# GPIB.net
KiCad netlist of a schematic drawn in Altium Designer
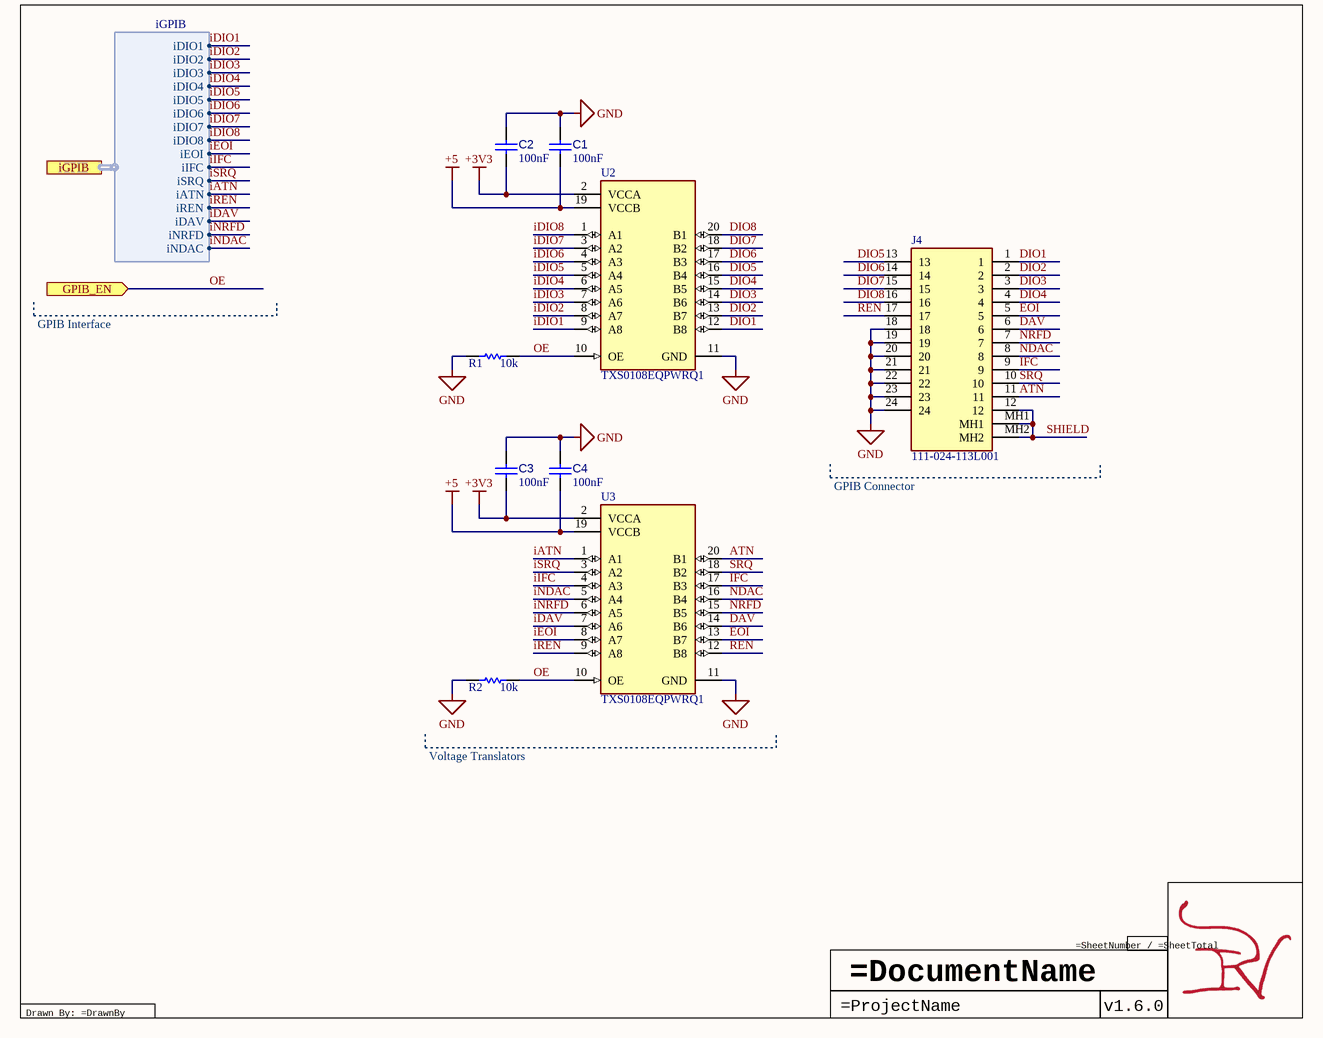
[diagram p0: GPIB.SchDoc]

(export (version "E")
  (design (tool "Eeschema 10.0.6"))
  (components
    (comp (ref "C1")
      (value "100nF")
      (footprint "CAP 0402_1005")
      (fields (field (name "TOLERANCE") "10%") (field (name "Comment") "CAP-NP-2"))
      (libsource (lib "IIT Motorsports") (part "CAP-NP-2"))
    )
    (comp (ref "C2")
      (value "100nF")
      (footprint "CAP 0402_1005")
      (fields (field (name "TOLERANCE") "10%") (field (name "Comment") "CAP-NP-2"))
      (libsource (lib "IIT Motorsports") (part "CAP-NP-2"))
    )
    (comp (ref "C3")
      (value "100nF")
      (footprint "CAP 0402_1005")
      (fields (field (name "TOLERANCE") "10%") (field (name "Comment") "CAP-NP-2"))
      (libsource (lib "IIT Motorsports") (part "CAP-NP-2"))
    )
    (comp (ref "C4")
      (value "100nF")
      (footprint "CAP 0402_1005")
      (fields (field (name "TOLERANCE") "10%") (field (name "Comment") "CAP-NP-2"))
      (libsource (lib "IIT Motorsports") (part "CAP-NP-2"))
    )
    (comp (ref "J4")
      (value "111-024-113L001")
      (footprint "111024113L001")
      (description "Telecom and Datacom Connector")
      (fields (field (name "MOUSER PART NUMBER") "636-111-024-113L001"))
      (libsource (lib "IIT Motorsports") (part "111-024-113L001"))
    )
    (comp (ref "R1")
      (value "10k")
      (footprint "RES 0402_1005")
      (fields
        (field (name "TOLERANCE") "1%")
        (field (name "POWER") "100mW")
        (field (name "Comment") "10K-0402-0.1/1")
      )
      (libsource (lib "IIT Motorsports") (part "RES"))
    )
    (comp (ref "R2")
      (value "10k")
      (footprint "RES 0402_1005")
      (fields
        (field (name "TOLERANCE") "1%")
        (field (name "POWER") "100mW")
        (field (name "Comment") "10K-0402-0.1/1")
      )
      (libsource (lib "IIT Motorsports") (part "RES"))
    )
    (comp (ref "U2")
      (value "TXS0108EQPWRQ1")
      (footprint "FP-PW0020A-IPC_B")
      (description "Interface Circuit, PDSO20")
      (libsource (lib "IIT Motorsports") (part "b852cf3f2c97e4a3d4172ee3f19d589"))
    )
    (comp (ref "U3")
      (value "TXS0108EQPWRQ1")
      (footprint "FP-PW0020A-IPC_B")
      (description "Interface Circuit, PDSO20")
      (libsource (lib "IIT Motorsports") (part "b852cf3f2c97e4a3d4172ee3f19d589"))
    )
  )
  (nets
    (net (code "2") (name "+3V3") (class "Default")
      (node (ref "C2") (pin "1") (pinfunction "1_1") (pintype "passive"))
      (node (ref "C3") (pin "1") (pinfunction "1_1") (pintype "passive"))
      (node (ref "U2") (pin "2") (pinfunction "VCCA_2") (pintype "power_in"))
      (node (ref "U3") (pin "2") (pinfunction "VCCA_2") (pintype "power_in"))
    )
    (net (code "3") (name "+5") (class "Default")
      (node (ref "C1") (pin "1") (pinfunction "1_1") (pintype "passive"))
      (node (ref "C4") (pin "1") (pinfunction "1_1") (pintype "passive"))
      (node (ref "U2") (pin "19") (pinfunction "VCCB_19") (pintype "power_in"))
      (node (ref "U3") (pin "19") (pinfunction "VCCB_19") (pintype "power_in"))
    )
    (net (code "4") (name "/ATN") (class "Default")
      (node (ref "J4") (pin "11") (pinfunction "11_11") (pintype "passive"))
      (node (ref "U3") (pin "20") (pinfunction "B1_20") (pintype "bidirectional"))
    )
    (net (code "5") (name "/DAV") (class "Default")
      (node (ref "J4") (pin "6") (pinfunction "6_6") (pintype "passive"))
      (node (ref "U3") (pin "14") (pinfunction "B6_14") (pintype "bidirectional"))
    )
    (net (code "6") (name "/DIO1") (class "Default")
      (node (ref "J4") (pin "1") (pinfunction "1_1") (pintype "passive"))
      (node (ref "U2") (pin "12") (pinfunction "B8_12") (pintype "bidirectional"))
    )
    (net (code "7") (name "/DIO2") (class "Default")
      (node (ref "J4") (pin "2") (pinfunction "2_2") (pintype "passive"))
      (node (ref "U2") (pin "13") (pinfunction "B7_13") (pintype "bidirectional"))
    )
    (net (code "8") (name "/DIO3") (class "Default")
      (node (ref "J4") (pin "3") (pinfunction "3_3") (pintype "passive"))
      (node (ref "U2") (pin "14") (pinfunction "B6_14") (pintype "bidirectional"))
    )
    (net (code "9") (name "/DIO4") (class "Default")
      (node (ref "J4") (pin "4") (pinfunction "4_4") (pintype "passive"))
      (node (ref "U2") (pin "15") (pinfunction "B5_15") (pintype "bidirectional"))
    )
    (net (code "10") (name "/DIO5") (class "Default")
      (node (ref "J4") (pin "13") (pinfunction "13_13") (pintype "passive"))
      (node (ref "U2") (pin "16") (pinfunction "B4_16") (pintype "bidirectional"))
    )
    (net (code "11") (name "/DIO6") (class "Default")
      (node (ref "J4") (pin "14") (pinfunction "14_14") (pintype "passive"))
      (node (ref "U2") (pin "17") (pinfunction "B3_17") (pintype "bidirectional"))
    )
    (net (code "12") (name "/DIO7") (class "Default")
      (node (ref "J4") (pin "15") (pinfunction "15_15") (pintype "passive"))
      (node (ref "U2") (pin "18") (pinfunction "B2_18") (pintype "bidirectional"))
    )
    (net (code "13") (name "/DIO8") (class "Default")
      (node (ref "J4") (pin "16") (pinfunction "16_16") (pintype "passive"))
      (node (ref "U2") (pin "20") (pinfunction "B1_20") (pintype "bidirectional"))
    )
    (net (code "14") (name "/EOI") (class "Default")
      (node (ref "J4") (pin "5") (pinfunction "5_5") (pintype "passive"))
      (node (ref "U3") (pin "13") (pinfunction "B7_13") (pintype "bidirectional"))
    )
    (net (code "15") (name "/IFC") (class "Default")
      (node (ref "J4") (pin "9") (pinfunction "9_9") (pintype "passive"))
      (node (ref "U3") (pin "17") (pinfunction "B3_17") (pintype "bidirectional"))
    )
    (net (code "16") (name "/NDAC") (class "Default")
      (node (ref "J4") (pin "8") (pinfunction "8_8") (pintype "passive"))
      (node (ref "U3") (pin "16") (pinfunction "B4_16") (pintype "bidirectional"))
    )
    (net (code "17") (name "/NRFD") (class "Default")
      (node (ref "J4") (pin "7") (pinfunction "7_7") (pintype "passive"))
      (node (ref "U3") (pin "15") (pinfunction "B5_15") (pintype "bidirectional"))
    )
    (net (code "18") (name "/OE") (class "Default")
      (node (ref "R1") (pin "2") (pinfunction "2_2") (pintype "passive"))
      (node (ref "R2") (pin "2") (pinfunction "2_2") (pintype "passive"))
      (node (ref "U2") (pin "10") (pinfunction "OE_10") (pintype "input"))
      (node (ref "U3") (pin "10") (pinfunction "OE_10") (pintype "input"))
    )
    (net (code "19") (name "/REN") (class "Default")
      (node (ref "J4") (pin "17") (pinfunction "17_17") (pintype "passive"))
      (node (ref "U3") (pin "12") (pinfunction "B8_12") (pintype "bidirectional"))
    )
    (net (code "20") (name "/SHIELD") (class "Default")
      (node (ref "J4") (pin "12") (pinfunction "12_12") (pintype "passive"))
      (node (ref "J4") (pin "MH1") (pinfunction "MH1_MH1") (pintype "passive"))
      (node (ref "J4") (pin "MH2") (pinfunction "MH2_MH2") (pintype "passive"))
    )
    (net (code "21") (name "/SRQ") (class "Default")
      (node (ref "J4") (pin "10") (pinfunction "10_10") (pintype "passive"))
      (node (ref "U3") (pin "18") (pinfunction "B2_18") (pintype "bidirectional"))
    )
    (net (code "22") (name "/iATN") (class "Default")
      (node (ref "U3") (pin "1") (pinfunction "A1_1") (pintype "bidirectional"))
    )
    (net (code "23") (name "/iDAV") (class "Default")
      (node (ref "U3") (pin "7") (pinfunction "A6_7") (pintype "bidirectional"))
    )
    (net (code "24") (name "/iDIO1") (class "Default")
      (node (ref "U2") (pin "9") (pinfunction "A8_9") (pintype "bidirectional"))
    )
    (net (code "25") (name "/iDIO2") (class "Default")
      (node (ref "U2") (pin "8") (pinfunction "A7_8") (pintype "bidirectional"))
    )
    (net (code "26") (name "/iDIO3") (class "Default")
      (node (ref "U2") (pin "7") (pinfunction "A6_7") (pintype "bidirectional"))
    )
    (net (code "27") (name "/iDIO4") (class "Default")
      (node (ref "U2") (pin "6") (pinfunction "A5_6") (pintype "bidirectional"))
    )
    (net (code "28") (name "/iDIO5") (class "Default")
      (node (ref "U2") (pin "5") (pinfunction "A4_5") (pintype "bidirectional"))
    )
    (net (code "29") (name "/iDIO6") (class "Default")
      (node (ref "U2") (pin "4") (pinfunction "A3_4") (pintype "bidirectional"))
    )
    (net (code "30") (name "/iDIO7") (class "Default")
      (node (ref "U2") (pin "3") (pinfunction "A2_3") (pintype "bidirectional"))
    )
    (net (code "31") (name "/iDIO8") (class "Default")
      (node (ref "U2") (pin "1") (pinfunction "A1_1") (pintype "bidirectional"))
    )
    (net (code "32") (name "/iEOI") (class "Default")
      (node (ref "U3") (pin "8") (pinfunction "A7_8") (pintype "bidirectional"))
    )
    (net (code "33") (name "/iIFC") (class "Default")
      (node (ref "U3") (pin "4") (pinfunction "A3_4") (pintype "bidirectional"))
    )
    (net (code "34") (name "/iNDAC") (class "Default")
      (node (ref "U3") (pin "5") (pinfunction "A4_5") (pintype "bidirectional"))
    )
    (net (code "35") (name "/iNRFD") (class "Default")
      (node (ref "U3") (pin "6") (pinfunction "A5_6") (pintype "bidirectional"))
    )
    (net (code "36") (name "/iREN") (class "Default")
      (node (ref "U3") (pin "9") (pinfunction "A8_9") (pintype "bidirectional"))
    )
    (net (code "37") (name "/iSRQ") (class "Default")
      (node (ref "U3") (pin "3") (pinfunction "A2_3") (pintype "bidirectional"))
    )
    (net (code "39") (name "GND") (class "Default")
      (node (ref "C1") (pin "2") (pinfunction "2_2") (pintype "passive"))
      (node (ref "C2") (pin "2") (pinfunction "2_2") (pintype "passive"))
      (node (ref "C3") (pin "2") (pinfunction "2_2") (pintype "passive"))
      (node (ref "C4") (pin "2") (pinfunction "2_2") (pintype "passive"))
      (node (ref "J4") (pin "18") (pinfunction "18_18") (pintype "passive"))
      (node (ref "J4") (pin "19") (pinfunction "19_19") (pintype "passive"))
      (node (ref "J4") (pin "20") (pinfunction "20_20") (pintype "passive"))
      (node (ref "J4") (pin "21") (pinfunction "21_21") (pintype "passive"))
      (node (ref "J4") (pin "22") (pinfunction "22_22") (pintype "passive"))
      (node (ref "J4") (pin "23") (pinfunction "23_23") (pintype "passive"))
      (node (ref "J4") (pin "24") (pinfunction "24_24") (pintype "passive"))
      (node (ref "R1") (pin "1") (pinfunction "1_1") (pintype "passive"))
      (node (ref "R2") (pin "1") (pinfunction "1_1") (pintype "passive"))
      (node (ref "U2") (pin "11") (pinfunction "GND_11") (pintype "power_in"))
      (node (ref "U3") (pin "11") (pinfunction "GND_11") (pintype "power_in"))
    )
  )
)
